# tama2_1.net
KiCad netlist of a schematic drawn in EAGLE
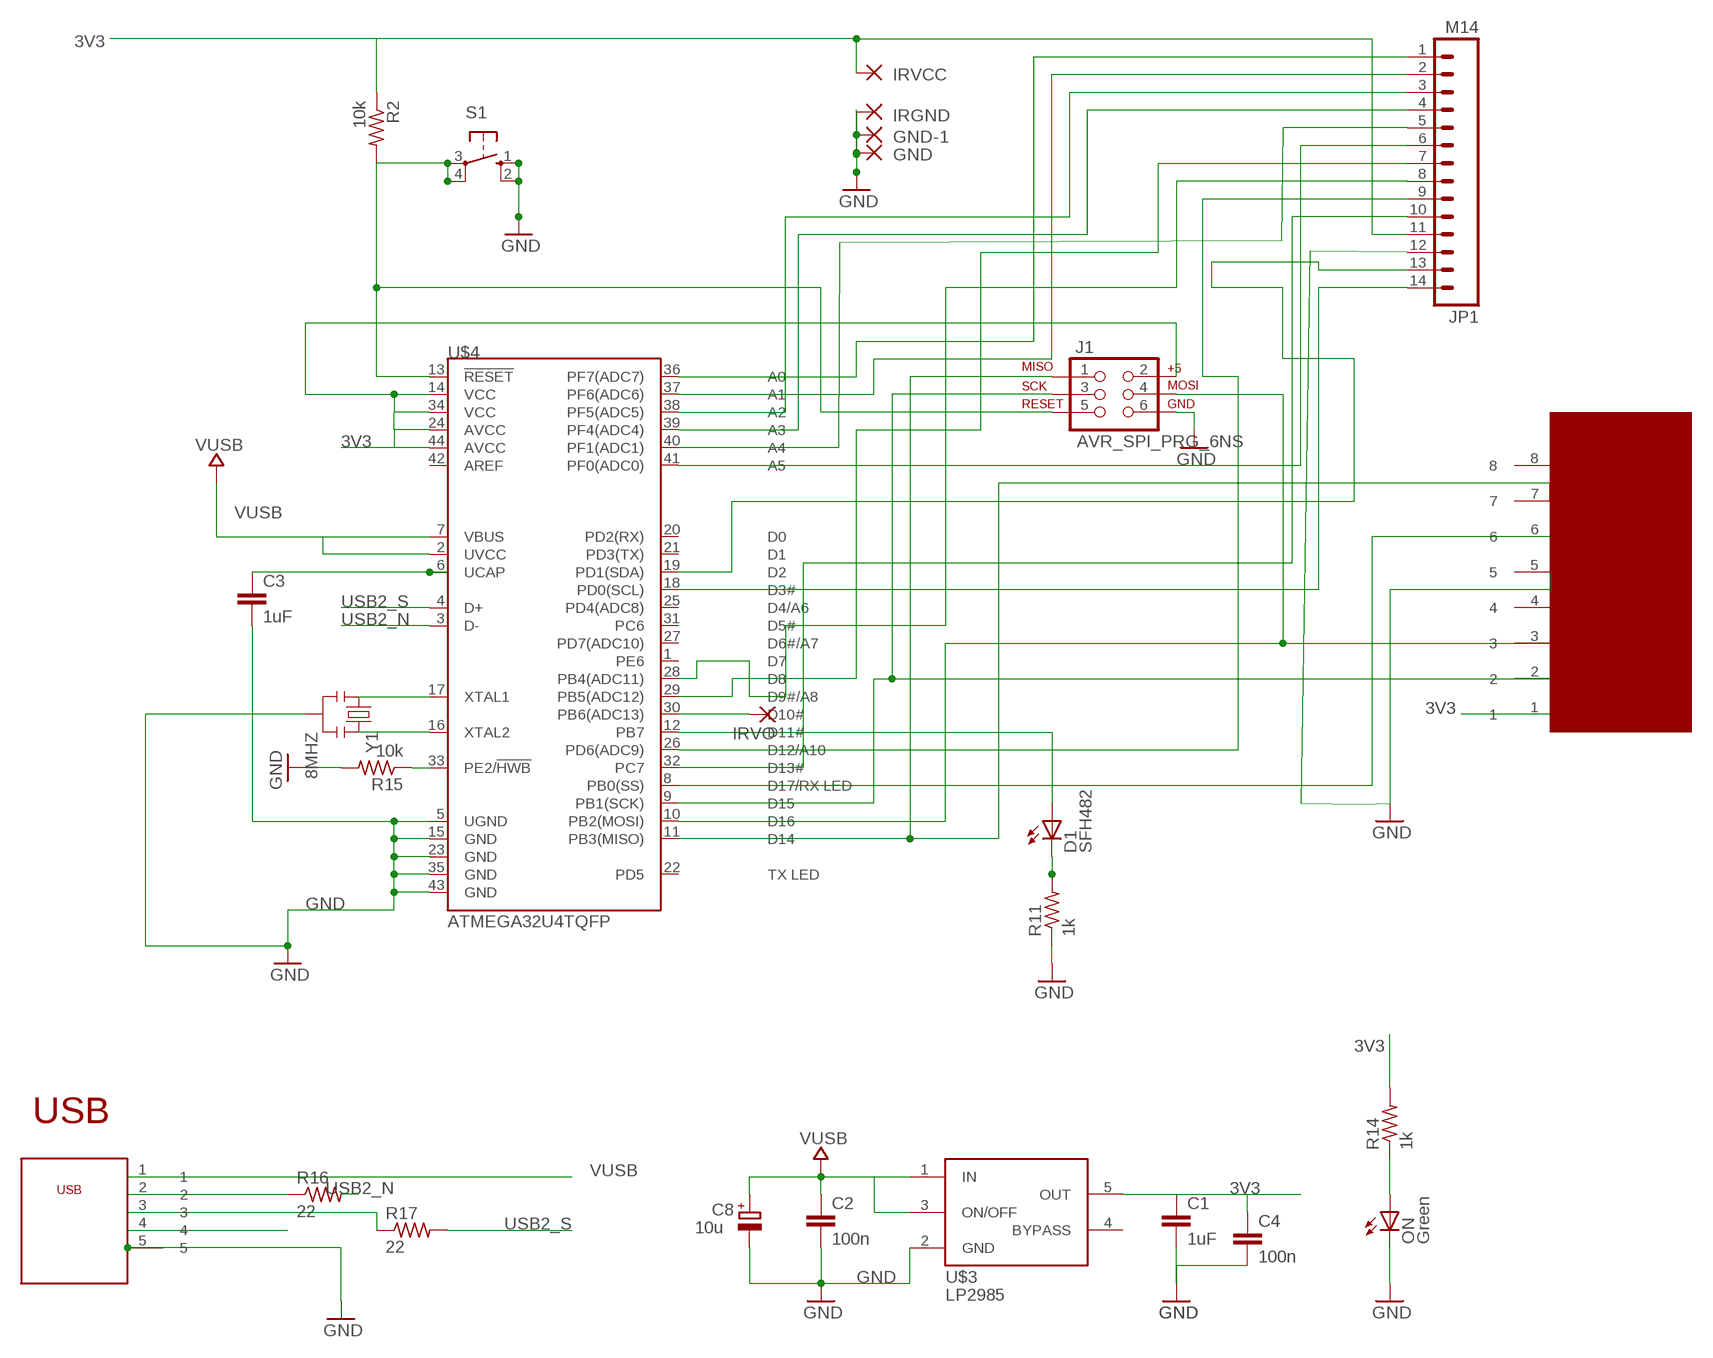
[diagram p0: schematic, sheet 1]

(export (version "E")
  (design (tool "Eeschema 10.0.6"))
  (components
    (comp (ref "C1")
      (value "1uF")
      (footprint "eagle-import:C1206")
      (libsource (lib "eagle-import") (part "C-EUC1206"))
    )
    (comp (ref "C2")
      (value "100n")
      (footprint "eagle-import:C1206")
      (libsource (lib "eagle-import") (part "C-EUC1206"))
    )
    (comp (ref "C3")
      (value "1uF")
      (footprint "eagle-import:C1206")
      (libsource (lib "eagle-import") (part "C-EUC1206"))
    )
    (comp (ref "C4")
      (value "100n")
      (footprint "eagle-import:C1206")
      (libsource (lib "eagle-import") (part "C-EUC1206"))
    )
    (comp (ref "C8")
      (value "10u")
      (footprint "eagle-import:SMC_B")
      (libsource (lib "eagle-import") (part "CPOL-EUSMCB"))
    )
    (comp (ref "D1")
      (value "SFH482")
      (footprint "eagle-import:SFH482")
      (libsource (lib "eagle-import") (part "SFH482"))
    )
    (comp (ref "GND")
      (value "2,15/1,0")
      (footprint "eagle-import:2,15_1,0")
      (libsource (lib "eagle-import") (part "2,15/1,0"))
    )
    (comp (ref "GND-1")
      (value "2,15/1,0")
      (footprint "eagle-import:2,15_1,0")
      (libsource (lib "eagle-import") (part "2,15/1,0"))
    )
    (comp (ref "IRGND")
      (value "2,15/1,0")
      (footprint "eagle-import:2,15_1,0")
      (libsource (lib "eagle-import") (part "2,15/1,0"))
    )
    (comp (ref "IRVCC")
      (value "2,15/1,0")
      (footprint "eagle-import:2,15_1,0")
      (libsource (lib "eagle-import") (part "2,15/1,0"))
    )
    (comp (ref "IRVO")
      (value "2,15/1,0")
      (footprint "eagle-import:2,15_1,0")
      (libsource (lib "eagle-import") (part "2,15/1,0"))
    )
    (comp (ref "J1")
      (value "AVR_SPI_PRG_6NS")
      (footprint "eagle-import:2X3-NS")
      (libsource (lib "eagle-import") (part "AVR_SPI_PRG_6NS"))
    )
    (comp (ref "JP1")
      (value "M14")
      (footprint "eagle-import:1X14")
      (libsource (lib "eagle-import") (part "M14"))
    )
    (comp (ref "ON")
      (value "Green")
      (footprint "eagle-import:CHIPLED_0805")
      (libsource (lib "eagle-import") (part "LEDCHIPLED_0805"))
    )
    (comp (ref "R2")
      (value "10k")
      (footprint "eagle-import:R1206")
      (libsource (lib "eagle-import") (part "R-US_R1206"))
    )
    (comp (ref "R11")
      (value "1k")
      (footprint "eagle-import:R1206")
      (libsource (lib "eagle-import") (part "R-US_R1206"))
    )
    (comp (ref "R14")
      (value "1k")
      (footprint "eagle-import:R1206")
      (libsource (lib "eagle-import") (part "R-US_R1206"))
    )
    (comp (ref "R15")
      (value "10k")
      (footprint "eagle-import:R1206")
      (libsource (lib "eagle-import") (part "R-US_R1206"))
    )
    (comp (ref "R16")
      (value "22")
      (footprint "eagle-import:R1206")
      (libsource (lib "eagle-import") (part "R-US_R1206"))
    )
    (comp (ref "R17")
      (value "22")
      (footprint "eagle-import:R1206")
      (libsource (lib "eagle-import") (part "R-US_R1206"))
    )
    (comp (ref "S1")
      (value "10-XX")
      (footprint "eagle-import:B3F-10XX")
      (fields (field (name "MPN") "B3F-1000"))
      (libsource (lib "eagle-import") (part "10-XX"))
    )
    (comp (ref "U$1")
      (value "TAMA")
      (footprint "eagle-import:TAMACONTACT")
      (libsource (lib "eagle-import") (part "TAMA"))
    )
    (comp (ref "U$2")
      (value "USB")
      (footprint "eagle-import:USB")
      (libsource (lib "eagle-import") (part "USB"))
    )
    (comp (ref "U$3")
      (value "LP2985")
      (footprint "eagle-import:SOT23-5")
      (libsource (lib "eagle-import") (part "LP2985"))
    )
    (comp (ref "U$4")
      (value "ATMEGA32U4TQFP")
      (footprint "eagle-import:SPARKFUN-DIGITALIC_TQFP44")
      (libsource (lib "eagle-import") (part "ATMEGA32U4TQFP"))
    )
    (comp (ref "Y1")
      (value "8MHZ")
      (footprint "eagle-import:RESONATOR-SMD")
      (libsource (lib "eagle-import") (part "RESONATOR8MHZ"))
    )
  )
  (nets
    (net (code "1") (name "/3V3") (class "Default")
      (node (ref "C1") (pin "1") (pinfunction "1_1") (pintype "passive"))
      (node (ref "C4") (pin "1") (pinfunction "1_1") (pintype "passive"))
      (node (ref "IRVCC") (pin "1") (pinfunction "P_1") (pintype "passive"))
      (node (ref "J1") (pin "2") (pinfunction "2_2") (pintype "passive"))
      (node (ref "JP1") (pin "11") (pinfunction "11_11") (pintype "passive"))
      (node (ref "R14") (pin "2") (pinfunction "2_2") (pintype "passive"))
      (node (ref "R2") (pin "1") (pinfunction "1_1") (pintype "passive"))
      (node (ref "U$1") (pin "1") (pinfunction "1_1") (pintype "bidirectional"))
      (node (ref "U$3") (pin "5") (pinfunction "OUT_5") (pintype "bidirectional"))
      (node (ref "U$4") (pin "14") (pinfunction "VCC_14") (pintype "bidirectional"))
      (node (ref "U$4") (pin "24") (pinfunction "AVCC_24") (pintype "bidirectional"))
      (node (ref "U$4") (pin "34") (pinfunction "VCC_34") (pintype "bidirectional"))
      (node (ref "U$4") (pin "44") (pinfunction "AVCC_44") (pintype "bidirectional"))
    )
    (net (code "2") (name "/USB2_N") (class "Default")
      (node (ref "R16") (pin "2") (pinfunction "2_2") (pintype "passive"))
      (node (ref "U$4") (pin "3") (pinfunction "D-_3") (pintype "bidirectional"))
    )
    (net (code "3") (name "/USB2_S") (class "Default")
      (node (ref "R17") (pin "2") (pinfunction "2_2") (pintype "passive"))
      (node (ref "U$4") (pin "4") (pinfunction "D+_4") (pintype "bidirectional"))
    )
    (net (code "4") (name "GND") (class "Default")
      (node (ref "C1") (pin "2") (pinfunction "2_2") (pintype "passive"))
      (node (ref "C2") (pin "2") (pinfunction "2_2") (pintype "passive"))
      (node (ref "C3") (pin "2") (pinfunction "2_2") (pintype "passive"))
      (node (ref "C4") (pin "2") (pinfunction "2_2") (pintype "passive"))
      (node (ref "C8") (pin "-") (pinfunction "-_-") (pintype "passive"))
      (node (ref "GND") (pin "1") (pinfunction "P_1") (pintype "passive"))
      (node (ref "GND-1") (pin "1") (pinfunction "P_1") (pintype "passive"))
      (node (ref "IRGND") (pin "1") (pinfunction "P_1") (pintype "passive"))
      (node (ref "J1") (pin "6") (pinfunction "6_6") (pintype "passive"))
      (node (ref "JP1") (pin "12") (pinfunction "12_12") (pintype "passive"))
      (node (ref "ON") (pin "C") (pinfunction "C_C") (pintype "passive"))
      (node (ref "R11") (pin "1") (pinfunction "1_1") (pintype "passive"))
      (node (ref "R15") (pin "2") (pinfunction "2_2") (pintype "passive"))
      (node (ref "S1") (pin "1") (pinfunction "S_1") (pintype "passive"))
      (node (ref "S1") (pin "2") (pinfunction "S1_2") (pintype "passive"))
      (node (ref "U$1") (pin "5") (pinfunction "5_5") (pintype "bidirectional"))
      (node (ref "U$2") (pin "5") (pinfunction "5_5") (pintype "bidirectional"))
      (node (ref "U$3") (pin "2") (pinfunction "GND_2") (pintype "bidirectional"))
      (node (ref "U$4") (pin "15") (pinfunction "GND_15") (pintype "bidirectional"))
      (node (ref "U$4") (pin "23") (pinfunction "GND_23") (pintype "bidirectional"))
      (node (ref "U$4") (pin "35") (pinfunction "GND_35") (pintype "bidirectional"))
      (node (ref "U$4") (pin "43") (pinfunction "GND_43") (pintype "bidirectional"))
      (node (ref "U$4") (pin "5") (pinfunction "UGND_5") (pintype "bidirectional"))
      (node (ref "Y1") (pin "2") (pinfunction "2_2") (pintype "passive"))
    )
    (net (code "5") (name "Net-(D1-C)") (class "Default")
      (node (ref "D1") (pin "K") (pinfunction "C_K") (pintype "passive"))
      (node (ref "R11") (pin "2") (pinfunction "2_2") (pintype "passive"))
    )
    (net (code "6") (name "Net-(IRVO-P)") (class "Default")
      (node (ref "IRVO") (pin "1") (pinfunction "P_1") (pintype "passive"))
      (node (ref "U$4") (pin "30") (pinfunction "PB6(ADC13)_30") (pintype "bidirectional"))
    )
    (net (code "7") (name "Net-(ON-PadA)") (class "Default")
      (node (ref "ON") (pin "A") (pinfunction "A_A") (pintype "passive"))
      (node (ref "R14") (pin "1") (pinfunction "1_1") (pintype "passive"))
    )
    (net (code "8") (name "Net-(R16-Pad1)") (class "Default")
      (node (ref "R16") (pin "1") (pinfunction "1_1") (pintype "passive"))
      (node (ref "U$2") (pin "2") (pinfunction "2_2") (pintype "bidirectional"))
    )
    (net (code "9") (name "Net-(R17-Pad1)") (class "Default")
      (node (ref "R17") (pin "1") (pinfunction "1_1") (pintype "passive"))
      (node (ref "U$2") (pin "3") (pinfunction "3_3") (pintype "bidirectional"))
    )
    (net (code "10") (name "Net-(S1-P)") (class "Default")
      (node (ref "J1") (pin "5") (pinfunction "5_5") (pintype "passive"))
      (node (ref "R2") (pin "2") (pinfunction "2_2") (pintype "passive"))
      (node (ref "S1") (pin "3") (pinfunction "P_3") (pintype "passive"))
      (node (ref "S1") (pin "4") (pinfunction "P1_4") (pintype "passive"))
      (node (ref "U$4") (pin "13") (pinfunction "~{RESET}_13") (pintype "bidirectional"))
    )
    (net (code "11") (name "Net-(U$4-PB0(SS))") (class "Default")
      (node (ref "U$1") (pin "6") (pinfunction "6_6") (pintype "bidirectional"))
      (node (ref "U$4") (pin "8") (pinfunction "PB0(SS)_8") (pintype "bidirectional"))
    )
    (net (code "12") (name "Net-(U$4-PB1(SCK))") (class "Default")
      (node (ref "J1") (pin "3") (pinfunction "3_3") (pintype "passive"))
      (node (ref "U$1") (pin "2") (pinfunction "2_2") (pintype "bidirectional"))
      (node (ref "U$4") (pin "9") (pinfunction "PB1(SCK)_9") (pintype "bidirectional"))
    )
    (net (code "13") (name "Net-(U$4-PB2(MOSI))") (class "Default")
      (node (ref "J1") (pin "4") (pinfunction "4_4") (pintype "passive"))
      (node (ref "U$1") (pin "3") (pinfunction "3_3") (pintype "bidirectional"))
      (node (ref "U$4") (pin "10") (pinfunction "PB2(MOSI)_10") (pintype "bidirectional"))
    )
    (net (code "14") (name "Net-(U$4-PB3(MISO))") (class "Default")
      (node (ref "J1") (pin "1") (pinfunction "1_1") (pintype "passive"))
      (node (ref "U$1") (pin "7") (pinfunction "7_7") (pintype "bidirectional"))
      (node (ref "U$4") (pin "11") (pinfunction "PB3(MISO)_11") (pintype "bidirectional"))
    )
    (net (code "15") (name "Net-(U$4-PB4(ADC11))") (class "Default")
      (node (ref "JP1") (pin "8") (pinfunction "8_8") (pintype "passive"))
      (node (ref "U$4") (pin "28") (pinfunction "PB4(ADC11)_28") (pintype "bidirectional"))
    )
    (net (code "16") (name "Net-(U$4-PB5(ADC12))") (class "Default")
      (node (ref "JP1") (pin "7") (pinfunction "7_7") (pintype "passive"))
      (node (ref "U$4") (pin "29") (pinfunction "PB5(ADC12)_29") (pintype "bidirectional"))
    )
    (net (code "17") (name "Net-(U$4-PB7)") (class "Default")
      (node (ref "D1") (pin "A") (pinfunction "A_A") (pintype "passive"))
      (node (ref "U$4") (pin "12") (pinfunction "PB7_12") (pintype "bidirectional"))
    )
    (net (code "18") (name "Net-(U$4-PC7)") (class "Default")
      (node (ref "JP1") (pin "10") (pinfunction "10_10") (pintype "passive"))
      (node (ref "U$4") (pin "32") (pinfunction "PC7_32") (pintype "bidirectional"))
    )
    (net (code "19") (name "Net-(U$4-PD0(SCL))") (class "Default")
      (node (ref "JP1") (pin "14") (pinfunction "14_14") (pintype "passive"))
      (node (ref "U$4") (pin "18") (pinfunction "PD0(SCL)_18") (pintype "bidirectional"))
    )
    (net (code "20") (name "Net-(U$4-PD1(SDA))") (class "Default")
      (node (ref "JP1") (pin "13") (pinfunction "13_13") (pintype "passive"))
      (node (ref "U$4") (pin "19") (pinfunction "PD1(SDA)_19") (pintype "bidirectional"))
    )
    (net (code "21") (name "Net-(U$4-PD6(ADC9))") (class "Default")
      (node (ref "JP1") (pin "9") (pinfunction "9_9") (pintype "passive"))
      (node (ref "U$4") (pin "26") (pinfunction "PD6(ADC9)_26") (pintype "bidirectional"))
    )
    (net (code "22") (name "Net-(U$4-PE2{slash}~{HWB})") (class "Default")
      (node (ref "R15") (pin "1") (pinfunction "1_1") (pintype "passive"))
      (node (ref "U$4") (pin "33") (pinfunction "PE2/~{HWB}_33") (pintype "bidirectional"))
    )
    (net (code "23") (name "Net-(U$4-PF0(ADC0))") (class "Default")
      (node (ref "JP1") (pin "6") (pinfunction "6_6") (pintype "passive"))
      (node (ref "U$4") (pin "41") (pinfunction "PF0(ADC0)_41") (pintype "bidirectional"))
    )
    (net (code "24") (name "Net-(U$4-PF1(ADC1))") (class "Default")
      (node (ref "JP1") (pin "5") (pinfunction "5_5") (pintype "passive"))
      (node (ref "U$4") (pin "40") (pinfunction "PF1(ADC1)_40") (pintype "bidirectional"))
    )
    (net (code "25") (name "Net-(U$4-PF4(ADC4))") (class "Default")
      (node (ref "JP1") (pin "4") (pinfunction "4_4") (pintype "passive"))
      (node (ref "U$4") (pin "39") (pinfunction "PF4(ADC4)_39") (pintype "bidirectional"))
    )
    (net (code "26") (name "Net-(U$4-PF5(ADC5))") (class "Default")
      (node (ref "JP1") (pin "3") (pinfunction "3_3") (pintype "passive"))
      (node (ref "U$4") (pin "38") (pinfunction "PF5(ADC5)_38") (pintype "bidirectional"))
    )
    (net (code "27") (name "Net-(U$4-PF6(ADC6))") (class "Default")
      (node (ref "JP1") (pin "2") (pinfunction "2_2") (pintype "passive"))
      (node (ref "U$4") (pin "37") (pinfunction "PF6(ADC6)_37") (pintype "bidirectional"))
    )
    (net (code "28") (name "Net-(U$4-PF7(ADC7))") (class "Default")
      (node (ref "JP1") (pin "1") (pinfunction "1_1") (pintype "passive"))
      (node (ref "U$4") (pin "36") (pinfunction "PF7(ADC7)_36") (pintype "bidirectional"))
    )
    (net (code "29") (name "Net-(U$4-UCAP)") (class "Default")
      (node (ref "C3") (pin "1") (pinfunction "1_1") (pintype "passive"))
      (node (ref "U$4") (pin "6") (pinfunction "UCAP_6") (pintype "bidirectional"))
    )
    (net (code "30") (name "Net-(U$4-XTAL1)") (class "Default")
      (node (ref "U$4") (pin "17") (pinfunction "XTAL1_17") (pintype "bidirectional"))
      (node (ref "Y1") (pin "1") (pinfunction "1_1") (pintype "passive"))
    )
    (net (code "31") (name "Net-(U$4-XTAL2)") (class "Default")
      (node (ref "U$4") (pin "16") (pinfunction "XTAL2_16") (pintype "bidirectional"))
      (node (ref "Y1") (pin "3") (pinfunction "3_3") (pintype "passive"))
    )
    (net (code "32") (name "VUSB") (class "Default")
      (node (ref "C2") (pin "1") (pinfunction "1_1") (pintype "passive"))
      (node (ref "C8") (pin "+") (pinfunction "+_+") (pintype "passive"))
      (node (ref "U$2") (pin "1") (pinfunction "1_1") (pintype "bidirectional"))
      (node (ref "U$3") (pin "1") (pinfunction "IN_1") (pintype "bidirectional"))
      (node (ref "U$3") (pin "3") (pinfunction "ON/OFF_3") (pintype "bidirectional"))
      (node (ref "U$4") (pin "2") (pinfunction "UVCC_2") (pintype "bidirectional"))
      (node (ref "U$4") (pin "7") (pinfunction "VBUS_7") (pintype "bidirectional"))
    )
    (net (code "33") (name "unconnected-(U$1-Pad4)") (class "Default")
      (node (ref "U$1") (pin "4") (pinfunction "4_4") (pintype "bidirectional"))
    )
    (net (code "34") (name "unconnected-(U$1-Pad8)") (class "Default")
      (node (ref "U$1") (pin "8") (pinfunction "8_8") (pintype "bidirectional"))
    )
    (net (code "35") (name "unconnected-(U$2-Pad4)") (class "Default")
      (node (ref "U$2") (pin "4") (pinfunction "4_4") (pintype "bidirectional"))
    )
    (net (code "36") (name "unconnected-(U$3-BYPASS-Pad4)") (class "Default")
      (node (ref "U$3") (pin "4") (pinfunction "BYPASS_4") (pintype "bidirectional"))
    )
    (net (code "37") (name "unconnected-(U$4-AREF-Pad42)") (class "Default")
      (node (ref "U$4") (pin "42") (pinfunction "AREF_42") (pintype "bidirectional"))
    )
    (net (code "38") (name "unconnected-(U$4-PC6-Pad31)") (class "Default")
      (node (ref "U$4") (pin "31") (pinfunction "PC6_31") (pintype "bidirectional"))
    )
    (net (code "39") (name "unconnected-(U$4-PD2(RX)-Pad20)") (class "Default")
      (node (ref "U$4") (pin "20") (pinfunction "PD2(RX)_20") (pintype "bidirectional"))
    )
    (net (code "40") (name "unconnected-(U$4-PD3(TX)-Pad21)") (class "Default")
      (node (ref "U$4") (pin "21") (pinfunction "PD3(TX)_21") (pintype "bidirectional"))
    )
    (net (code "41") (name "unconnected-(U$4-PD4(ADC8)-Pad25)") (class "Default")
      (node (ref "U$4") (pin "25") (pinfunction "PD4(ADC8)_25") (pintype "bidirectional"))
    )
    (net (code "42") (name "unconnected-(U$4-PD5-Pad22)") (class "Default")
      (node (ref "U$4") (pin "22") (pinfunction "PD5_22") (pintype "bidirectional"))
    )
    (net (code "43") (name "unconnected-(U$4-PD7(ADC10)-Pad27)") (class "Default")
      (node (ref "U$4") (pin "27") (pinfunction "PD7(ADC10)_27") (pintype "bidirectional"))
    )
    (net (code "44") (name "unconnected-(U$4-PE6-Pad1)") (class "Default")
      (node (ref "U$4") (pin "1") (pinfunction "PE6_1") (pintype "bidirectional"))
    )
  )
)
